# ADE-25_13cm.net
KiCad netlist of a schematic drawn in EAGLE
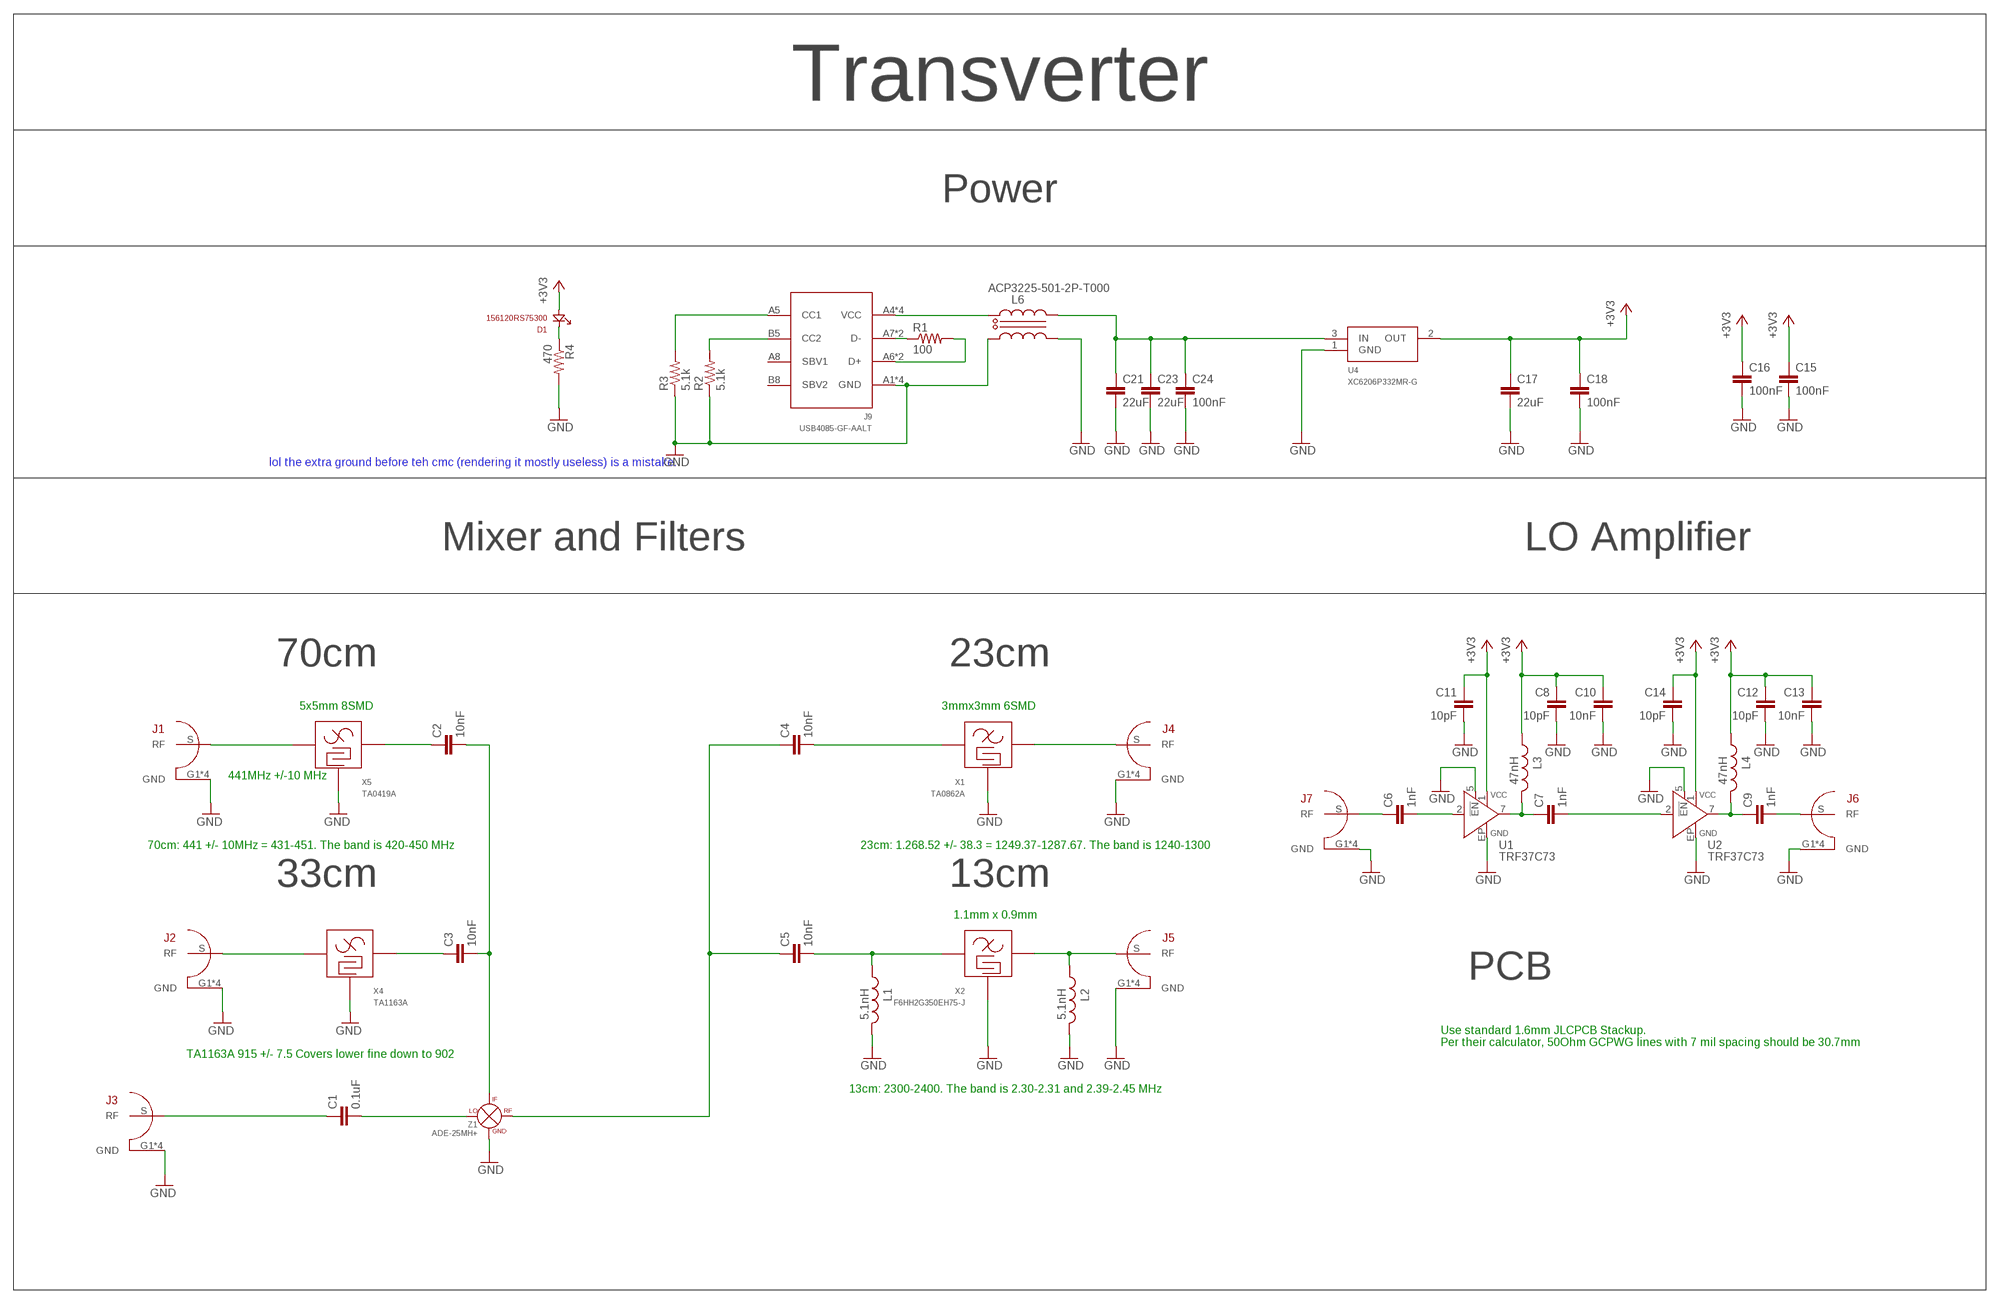
[diagram p0: schematic, sheet 1]

(export (version "E")
  (design (tool "Eeschema 10.0.6"))
  (components
    (comp (ref "C1")
      (value "0.1uF")
      (footprint "eagle-import:0603")
      (libsource (lib "eagle-import") (part "0603_CAPACITOR"))
    )
    (comp (ref "C2")
      (value "10nF")
      (footprint "eagle-import:0603")
      (libsource (lib "eagle-import") (part "0603_CAPACITOR"))
    )
    (comp (ref "C3")
      (value "10nF")
      (footprint "eagle-import:0603")
      (libsource (lib "eagle-import") (part "0603_CAPACITOR"))
    )
    (comp (ref "C4")
      (value "10nF")
      (footprint "eagle-import:0603")
      (libsource (lib "eagle-import") (part "0603_CAPACITOR"))
    )
    (comp (ref "C5")
      (value "10nF")
      (footprint "eagle-import:0603")
      (libsource (lib "eagle-import") (part "0603_CAPACITOR"))
    )
    (comp (ref "C6")
      (value "1nF")
      (footprint "eagle-import:0603")
      (libsource (lib "eagle-import") (part "0603_CAPACITOR"))
    )
    (comp (ref "C7")
      (value "1nF")
      (footprint "eagle-import:0603")
      (libsource (lib "eagle-import") (part "0603_CAPACITOR"))
    )
    (comp (ref "C8")
      (value "10pF")
      (footprint "eagle-import:0402_INDUCTOR")
      (libsource (lib "eagle-import") (part "0402_CAPACITOR"))
    )
    (comp (ref "C9")
      (value "1nF")
      (footprint "eagle-import:0603")
      (libsource (lib "eagle-import") (part "0603_CAPACITOR"))
    )
    (comp (ref "C10")
      (value "10nF")
      (footprint "eagle-import:0402_INDUCTOR")
      (libsource (lib "eagle-import") (part "0402_CAPACITOR"))
    )
    (comp (ref "C11")
      (value "10pF")
      (footprint "eagle-import:0402_INDUCTOR")
      (libsource (lib "eagle-import") (part "0402_CAPACITOR"))
    )
    (comp (ref "C12")
      (value "10pF")
      (footprint "eagle-import:0402_INDUCTOR")
      (libsource (lib "eagle-import") (part "0402_CAPACITOR"))
    )
    (comp (ref "C13")
      (value "10nF")
      (footprint "eagle-import:0402_INDUCTOR")
      (libsource (lib "eagle-import") (part "0402_CAPACITOR"))
    )
    (comp (ref "C14")
      (value "10pF")
      (footprint "eagle-import:0402_INDUCTOR")
      (libsource (lib "eagle-import") (part "0402_CAPACITOR"))
    )
    (comp (ref "C15")
      (value "100nF")
      (footprint "eagle-import:0603")
      (libsource (lib "eagle-import") (part "0603_CAPACITOR"))
    )
    (comp (ref "C16")
      (value "100nF")
      (footprint "eagle-import:0603")
      (libsource (lib "eagle-import") (part "0603_CAPACITOR"))
    )
    (comp (ref "C17")
      (value "22uF")
      (footprint "eagle-import:C1206")
      (libsource (lib "eagle-import") (part "C-EUC1206"))
    )
    (comp (ref "C18")
      (value "100nF")
      (footprint "eagle-import:0603")
      (libsource (lib "eagle-import") (part "0603_CAPACITOR"))
    )
    (comp (ref "C21")
      (value "22uF")
      (footprint "eagle-import:C1206")
      (libsource (lib "eagle-import") (part "C-EUC1206"))
    )
    (comp (ref "C23")
      (value "22uF")
      (footprint "eagle-import:C1206")
      (libsource (lib "eagle-import") (part "C-EUC1206"))
    )
    (comp (ref "C24")
      (value "100nF")
      (footprint "eagle-import:0603")
      (libsource (lib "eagle-import") (part "0603_CAPACITOR"))
    )
    (comp (ref "D1")
      (value "156120RS75300")
      (footprint "eagle-import:1206_REV")
      (fields (field (name "PARTNO") "732-5031-1-ND"))
      (libsource (lib "eagle-import") (part "156120RS75300"))
    )
    (comp (ref "J1")
      (value "0733910070")
      (footprint "eagle-import:CONREVSMA008-G")
      (fields (field (name "PARTNO") "WM5544-ND"))
      (libsource (lib "eagle-import") (part "0733910070"))
    )
    (comp (ref "J2")
      (value "0733910070")
      (footprint "eagle-import:CONREVSMA008-G")
      (fields (field (name "PARTNO") "WM5544-ND"))
      (libsource (lib "eagle-import") (part "0733910070"))
    )
    (comp (ref "J3")
      (value "0733910070")
      (footprint "eagle-import:CONREVSMA008-G")
      (fields (field (name "PARTNO") "WM5544-ND"))
      (libsource (lib "eagle-import") (part "0733910070"))
    )
    (comp (ref "J4")
      (value "0733910070")
      (footprint "eagle-import:CONREVSMA008-G")
      (fields (field (name "PARTNO") "WM5544-ND"))
      (libsource (lib "eagle-import") (part "0733910070"))
    )
    (comp (ref "J5")
      (value "0733910070")
      (footprint "eagle-import:CONREVSMA008-G")
      (fields (field (name "PARTNO") "WM5544-ND"))
      (libsource (lib "eagle-import") (part "0733910070"))
    )
    (comp (ref "J6")
      (value "0733910070")
      (footprint "eagle-import:CONREVSMA008-G")
      (fields (field (name "PARTNO") "WM5544-ND"))
      (libsource (lib "eagle-import") (part "0733910070"))
    )
    (comp (ref "J7")
      (value "0733910070")
      (footprint "eagle-import:CONREVSMA008-G")
      (fields (field (name "PARTNO") "WM5544-ND"))
      (libsource (lib "eagle-import") (part "0733910070"))
    )
    (comp (ref "J9")
      (value "USB4085-GF-AALT")
      (footprint "eagle-import:USBC2")
      (libsource (lib "eagle-import") (part "USB4085-GF-AALT"))
    )
    (comp (ref "L1")
      (value "5.1nH")
      (footprint "eagle-import:0402_INDUCTOR")
      (libsource (lib "eagle-import") (part "0402_INDUCTOR"))
    )
    (comp (ref "L2")
      (value "5.1nH")
      (footprint "eagle-import:0402_INDUCTOR")
      (libsource (lib "eagle-import") (part "0402_INDUCTOR"))
    )
    (comp (ref "L3")
      (value "47nH")
      (footprint "eagle-import:0402_INDUCTOR")
      (libsource (lib "eagle-import") (part "0402_INDUCTOR"))
    )
    (comp (ref "L4")
      (value "47nH")
      (footprint "eagle-import:0402_INDUCTOR")
      (libsource (lib "eagle-import") (part "0402_INDUCTOR"))
    )
    (comp (ref "L6")
      (value "ACP3225-501-2P-T000")
      (footprint "eagle-import:3225")
      (fields (field (name "PARTNO") "445-172408-1-ND"))
      (libsource (lib "eagle-import") (part "ACP3225-501-2P-T000"))
    )
    (comp (ref "R1")
      (value "100")
      (footprint "eagle-import:0603")
      (libsource (lib "eagle-import") (part "0603_RESISTOR"))
    )
    (comp (ref "R2")
      (value "5.1k")
      (footprint "eagle-import:0603")
      (libsource (lib "eagle-import") (part "0603_RESISTOR"))
    )
    (comp (ref "R3")
      (value "5.1k")
      (footprint "eagle-import:0603")
      (libsource (lib "eagle-import") (part "0603_RESISTOR"))
    )
    (comp (ref "R4")
      (value "470")
      (footprint "eagle-import:0603")
      (libsource (lib "eagle-import") (part "0603_RESISTOR"))
    )
    (comp (ref "U1")
      (value "TRF37C73")
      (footprint "eagle-import:8WSON2X2")
      (libsource (lib "eagle-import") (part "TRF37C73"))
    )
    (comp (ref "U2")
      (value "TRF37C73")
      (footprint "eagle-import:8WSON2X2")
      (libsource (lib "eagle-import") (part "TRF37C73"))
    )
    (comp (ref "U4")
      (value "XC6206P332MR-G")
      (footprint "eagle-import:SOT23-3_CENTERED")
      (libsource (lib "eagle-import") (part "XC6206P332MR-G"))
    )
    (comp (ref "X1")
      (value "TA0862A")
      (footprint "eagle-import:TA0862A")
      (fields (field (name "PARTNO") "4606-TA0862ACT-ND"))
      (libsource (lib "eagle-import") (part "TA0862A"))
    )
    (comp (ref "X2")
      (value "F6HH2G350EH75-J")
      (footprint "eagle-import:EH75")
      (fields (field (name "PARTNO") "587-F6HH2G350EH75-JCT-ND"))
      (libsource (lib "eagle-import") (part "F6HH2G350EH75-J"))
    )
    (comp (ref "X4")
      (value "TA1163A")
      (footprint "eagle-import:TA0862A")
      (fields (field (name "PARTNO") "4606-TA0862ACT-ND"))
      (libsource (lib "eagle-import") (part "TA0862A"))
    )
    (comp (ref "X5")
      (value "TA0419A")
      (footprint "eagle-import:TAO419")
      (fields (field (name "PARTNO") "4606-TA0419ACT-ND"))
      (libsource (lib "eagle-import") (part "TA0419A"))
    )
    (comp (ref "Z1")
      (value "ADE-25MH+")
      (footprint "eagle-import:CD")
      (fields (field (name "PARTNO") "3157-ADE-25MH+CT-ND"))
      (libsource (lib "eagle-import") (part "ADE-25MH+"))
    )
  )
  (nets
    (net (code "1") (name "+3V3") (class "Default")
      (node (ref "C10") (pin "P$1") (pinfunction "1_P$1") (pintype "passive"))
      (node (ref "C11") (pin "P$1") (pinfunction "1_P$1") (pintype "passive"))
      (node (ref "C12") (pin "P$1") (pinfunction "1_P$1") (pintype "passive"))
      (node (ref "C13") (pin "P$1") (pinfunction "1_P$1") (pintype "passive"))
      (node (ref "C14") (pin "P$1") (pinfunction "1_P$1") (pintype "passive"))
      (node (ref "C15") (pin "1") (pinfunction "1_1") (pintype "passive"))
      (node (ref "C16") (pin "1") (pinfunction "1_1") (pintype "passive"))
      (node (ref "C17") (pin "1") (pinfunction "1_1") (pintype "passive"))
      (node (ref "C18") (pin "1") (pinfunction "1_1") (pintype "passive"))
      (node (ref "C8") (pin "P$1") (pinfunction "1_P$1") (pintype "passive"))
      (node (ref "D1") (pin "A") (pinfunction "A_A") (pintype "bidirectional"))
      (node (ref "L3") (pin "P$1") (pinfunction "P$1_P$1") (pintype "bidirectional"))
      (node (ref "L4") (pin "P$1") (pinfunction "P$1_P$1") (pintype "bidirectional"))
      (node (ref "U1") (pin "1") (pinfunction "+VS_1") (pintype "input"))
      (node (ref "U2") (pin "1") (pinfunction "+VS_1") (pintype "input"))
      (node (ref "U4") (pin "2") (pinfunction "OUT_2") (pintype "bidirectional"))
    )
    (net (code "2") (name "GND") (class "Default")
      (node (ref "C10") (pin "P$2") (pinfunction "2_P$2") (pintype "passive"))
      (node (ref "C11") (pin "P$2") (pinfunction "2_P$2") (pintype "passive"))
      (node (ref "C12") (pin "P$2") (pinfunction "2_P$2") (pintype "passive"))
      (node (ref "C13") (pin "P$2") (pinfunction "2_P$2") (pintype "passive"))
      (node (ref "C14") (pin "P$2") (pinfunction "2_P$2") (pintype "passive"))
      (node (ref "C15") (pin "2") (pinfunction "2_2") (pintype "passive"))
      (node (ref "C16") (pin "2") (pinfunction "2_2") (pintype "passive"))
      (node (ref "C17") (pin "2") (pinfunction "2_2") (pintype "passive"))
      (node (ref "C18") (pin "2") (pinfunction "2_2") (pintype "passive"))
      (node (ref "C21") (pin "2") (pinfunction "2_2") (pintype "passive"))
      (node (ref "C23") (pin "2") (pinfunction "2_2") (pintype "passive"))
      (node (ref "C24") (pin "2") (pinfunction "2_2") (pintype "passive"))
      (node (ref "C8") (pin "P$2") (pinfunction "2_P$2") (pintype "passive"))
      (node (ref "J1") (pin "G1") (pinfunction "GND_G1") (pintype "bidirectional"))
      (node (ref "J1") (pin "G2") (pinfunction "GND_G2") (pintype "bidirectional"))
      (node (ref "J1") (pin "G3") (pinfunction "GND_G3") (pintype "bidirectional"))
      (node (ref "J1") (pin "G4") (pinfunction "GND_G4") (pintype "bidirectional"))
      (node (ref "J2") (pin "G1") (pinfunction "GND_G1") (pintype "bidirectional"))
      (node (ref "J2") (pin "G2") (pinfunction "GND_G2") (pintype "bidirectional"))
      (node (ref "J2") (pin "G3") (pinfunction "GND_G3") (pintype "bidirectional"))
      (node (ref "J2") (pin "G4") (pinfunction "GND_G4") (pintype "bidirectional"))
      (node (ref "J3") (pin "G1") (pinfunction "GND_G1") (pintype "bidirectional"))
      (node (ref "J3") (pin "G2") (pinfunction "GND_G2") (pintype "bidirectional"))
      (node (ref "J3") (pin "G3") (pinfunction "GND_G3") (pintype "bidirectional"))
      (node (ref "J3") (pin "G4") (pinfunction "GND_G4") (pintype "bidirectional"))
      (node (ref "J4") (pin "G1") (pinfunction "GND_G1") (pintype "bidirectional"))
      (node (ref "J4") (pin "G2") (pinfunction "GND_G2") (pintype "bidirectional"))
      (node (ref "J4") (pin "G3") (pinfunction "GND_G3") (pintype "bidirectional"))
      (node (ref "J4") (pin "G4") (pinfunction "GND_G4") (pintype "bidirectional"))
      (node (ref "J5") (pin "G1") (pinfunction "GND_G1") (pintype "bidirectional"))
      (node (ref "J5") (pin "G2") (pinfunction "GND_G2") (pintype "bidirectional"))
      (node (ref "J5") (pin "G3") (pinfunction "GND_G3") (pintype "bidirectional"))
      (node (ref "J5") (pin "G4") (pinfunction "GND_G4") (pintype "bidirectional"))
      (node (ref "J6") (pin "G1") (pinfunction "GND_G1") (pintype "bidirectional"))
      (node (ref "J6") (pin "G2") (pinfunction "GND_G2") (pintype "bidirectional"))
      (node (ref "J6") (pin "G3") (pinfunction "GND_G3") (pintype "bidirectional"))
      (node (ref "J6") (pin "G4") (pinfunction "GND_G4") (pintype "bidirectional"))
      (node (ref "J7") (pin "G1") (pinfunction "GND_G1") (pintype "bidirectional"))
      (node (ref "J7") (pin "G2") (pinfunction "GND_G2") (pintype "bidirectional"))
      (node (ref "J7") (pin "G3") (pinfunction "GND_G3") (pintype "bidirectional"))
      (node (ref "J7") (pin "G4") (pinfunction "GND_G4") (pintype "bidirectional"))
      (node (ref "J9") (pin "A1") (pinfunction "GND_A1") (pintype "bidirectional"))
      (node (ref "J9") (pin "A12") (pinfunction "GND_A12") (pintype "bidirectional"))
      (node (ref "J9") (pin "B1") (pinfunction "GND_B1") (pintype "bidirectional"))
      (node (ref "J9") (pin "B12") (pinfunction "GND_B12") (pintype "bidirectional"))
      (node (ref "L1") (pin "P$2") (pinfunction "P$2_P$2") (pintype "bidirectional"))
      (node (ref "L2") (pin "P$2") (pinfunction "P$2_P$2") (pintype "bidirectional"))
      (node (ref "L6") (pin "2") (pinfunction "2IN_2") (pintype "bidirectional"))
      (node (ref "L6") (pin "3") (pinfunction "2OUT_3") (pintype "bidirectional"))
      (node (ref "R2") (pin "1") (pinfunction "1_1") (pintype "passive"))
      (node (ref "R3") (pin "1") (pinfunction "1_1") (pintype "passive"))
      (node (ref "R4") (pin "2") (pinfunction "2_2") (pintype "passive"))
      (node (ref "U1") (pin "5") (pinfunction "~{EN}_5") (pintype "bidirectional"))
      (node (ref "U1") (pin "EP") (pinfunction "-VS_EP") (pintype "input"))
      (node (ref "U2") (pin "5") (pinfunction "~{EN}_5") (pintype "bidirectional"))
      (node (ref "U2") (pin "EP") (pinfunction "-VS_EP") (pintype "input"))
      (node (ref "U4") (pin "1") (pinfunction "GND_1") (pintype "bidirectional"))
      (node (ref "X1") (pin "A") (pinfunction "GND_A") (pintype "bidirectional"))
      (node (ref "X1") (pin "C") (pinfunction "GND_C") (pintype "bidirectional"))
      (node (ref "X1") (pin "D") (pinfunction "GND_D") (pintype "bidirectional"))
      (node (ref "X1") (pin "F") (pinfunction "GND_F") (pintype "bidirectional"))
      (node (ref "X2") (pin "2") (pinfunction "GND_2") (pintype "bidirectional"))
      (node (ref "X2") (pin "3") (pinfunction "GND_3") (pintype "bidirectional"))
      (node (ref "X2") (pin "5") (pinfunction "GND_5") (pintype "bidirectional"))
      (node (ref "X4") (pin "A") (pinfunction "GND_A") (pintype "bidirectional"))
      (node (ref "X4") (pin "C") (pinfunction "GND_C") (pintype "bidirectional"))
      (node (ref "X4") (pin "D") (pinfunction "GND_D") (pintype "bidirectional"))
      (node (ref "X4") (pin "F") (pinfunction "GND_F") (pintype "bidirectional"))
      (node (ref "X5") (pin "1") (pinfunction "GND_1") (pintype "bidirectional"))
      (node (ref "X5") (pin "3") (pinfunction "GND_3") (pintype "bidirectional"))
      (node (ref "X5") (pin "4") (pinfunction "GND_4") (pintype "bidirectional"))
      (node (ref "X5") (pin "5") (pinfunction "GND_5") (pintype "bidirectional"))
      (node (ref "X5") (pin "7") (pinfunction "GND_7") (pintype "bidirectional"))
      (node (ref "X5") (pin "8") (pinfunction "GND_8") (pintype "bidirectional"))
      (node (ref "Z1") (pin "1") (pinfunction "GND_1") (pintype "bidirectional"))
      (node (ref "Z1") (pin "4") (pinfunction "GND_4") (pintype "bidirectional"))
      (node (ref "Z1") (pin "5") (pinfunction "GND_5") (pintype "bidirectional"))
    )
    (net (code "3") (name "Net-(D1-PadK)") (class "Default")
      (node (ref "D1") (pin "K") (pinfunction "K_K") (pintype "bidirectional"))
      (node (ref "R4") (pin "1") (pinfunction "1_1") (pintype "passive"))
    )
    (net (code "4") (name "Net-(J1-RF)") (class "Default")
      (node (ref "J1") (pin "S") (pinfunction "RF_S") (pintype "bidirectional"))
      (node (ref "X5") (pin "6") (pinfunction "P$2_6") (pintype "bidirectional"))
    )
    (net (code "5") (name "Net-(J2-RF)") (class "Default")
      (node (ref "J2") (pin "S") (pinfunction "RF_S") (pintype "bidirectional"))
      (node (ref "X4") (pin "E") (pinfunction "P$2_E") (pintype "bidirectional"))
    )
    (net (code "6") (name "Net-(J3-RF)") (class "Default")
      (node (ref "C1") (pin "1") (pinfunction "1_1") (pintype "passive"))
      (node (ref "J3") (pin "S") (pinfunction "RF_S") (pintype "bidirectional"))
    )
    (net (code "7") (name "Net-(J4-RF)") (class "Default")
      (node (ref "J4") (pin "S") (pinfunction "RF_S") (pintype "bidirectional"))
      (node (ref "X1") (pin "E") (pinfunction "P$2_E") (pintype "bidirectional"))
    )
    (net (code "8") (name "Net-(J5-RF)") (class "Default")
      (node (ref "J5") (pin "S") (pinfunction "RF_S") (pintype "bidirectional"))
      (node (ref "L2") (pin "P$1") (pinfunction "P$1_P$1") (pintype "bidirectional"))
      (node (ref "X2") (pin "4") (pinfunction "P$2_4") (pintype "bidirectional"))
    )
    (net (code "9") (name "Net-(J6-RF)") (class "Default")
      (node (ref "C9") (pin "2") (pinfunction "2_2") (pintype "passive"))
      (node (ref "J6") (pin "S") (pinfunction "RF_S") (pintype "bidirectional"))
    )
    (net (code "10") (name "Net-(J7-RF)") (class "Default")
      (node (ref "C6") (pin "1") (pinfunction "1_1") (pintype "passive"))
      (node (ref "J7") (pin "S") (pinfunction "RF_S") (pintype "bidirectional"))
    )
    (net (code "11") (name "Net-(J9-CC1)") (class "Default")
      (node (ref "J9") (pin "A5") (pinfunction "CC1_A5") (pintype "bidirectional"))
      (node (ref "R3") (pin "2") (pinfunction "2_2") (pintype "passive"))
    )
    (net (code "12") (name "Net-(J9-CC2)") (class "Default")
      (node (ref "J9") (pin "B5") (pinfunction "CC2_B5") (pintype "bidirectional"))
      (node (ref "R2") (pin "2") (pinfunction "2_2") (pintype "passive"))
    )
    (net (code "13") (name "Net-(J9-D+-PadA6)") (class "Default")
      (node (ref "J9") (pin "A6") (pinfunction "D+_A6") (pintype "bidirectional"))
      (node (ref "J9") (pin "B6") (pinfunction "D+_B6") (pintype "bidirectional"))
      (node (ref "R1") (pin "2") (pinfunction "2_2") (pintype "passive"))
    )
    (net (code "14") (name "Net-(J9-D--PadA7)") (class "Default")
      (node (ref "J9") (pin "A7") (pinfunction "D-_A7") (pintype "bidirectional"))
      (node (ref "J9") (pin "B7") (pinfunction "D-_B7") (pintype "bidirectional"))
      (node (ref "R1") (pin "1") (pinfunction "1_1") (pintype "passive"))
    )
    (net (code "15") (name "Net-(L6-1IN)") (class "Default")
      (node (ref "J9") (pin "A4") (pinfunction "VCC_A4") (pintype "bidirectional"))
      (node (ref "J9") (pin "A9") (pinfunction "VCC_A9") (pintype "bidirectional"))
      (node (ref "J9") (pin "B4") (pinfunction "VCC_B4") (pintype "bidirectional"))
      (node (ref "J9") (pin "B9") (pinfunction "VCC_B9") (pintype "bidirectional"))
      (node (ref "L6") (pin "1") (pinfunction "1IN_1") (pintype "bidirectional"))
    )
    (net (code "16") (name "Net-(L6-1OUT)") (class "Default")
      (node (ref "C21") (pin "1") (pinfunction "1_1") (pintype "passive"))
      (node (ref "C23") (pin "1") (pinfunction "1_1") (pintype "passive"))
      (node (ref "C24") (pin "1") (pinfunction "1_1") (pintype "passive"))
      (node (ref "L6") (pin "4") (pinfunction "1OUT_4") (pintype "bidirectional"))
      (node (ref "U4") (pin "3") (pinfunction "IN_3") (pintype "bidirectional"))
    )
    (net (code "17") (name "Net-(U1-IN)") (class "Default")
      (node (ref "C6") (pin "2") (pinfunction "2_2") (pintype "passive"))
      (node (ref "U1") (pin "2") (pinfunction "IN_2") (pintype "input"))
    )
    (net (code "18") (name "Net-(U1-OUT)") (class "Default")
      (node (ref "C7") (pin "1") (pinfunction "1_1") (pintype "passive"))
      (node (ref "L3") (pin "P$2") (pinfunction "P$2_P$2") (pintype "bidirectional"))
      (node (ref "U1") (pin "7") (pinfunction "OUT_7") (pintype "output"))
    )
    (net (code "19") (name "Net-(U2-IN)") (class "Default")
      (node (ref "C7") (pin "2") (pinfunction "2_2") (pintype "passive"))
      (node (ref "U2") (pin "2") (pinfunction "IN_2") (pintype "input"))
    )
    (net (code "20") (name "Net-(U2-OUT)") (class "Default")
      (node (ref "C9") (pin "1") (pinfunction "1_1") (pintype "passive"))
      (node (ref "L4") (pin "P$2") (pinfunction "P$2_P$2") (pintype "bidirectional"))
      (node (ref "U2") (pin "7") (pinfunction "OUT_7") (pintype "output"))
    )
    (net (code "21") (name "Net-(X1-P$1)") (class "Default")
      (node (ref "C4") (pin "2") (pinfunction "2_2") (pintype "passive"))
      (node (ref "X1") (pin "B") (pinfunction "P$1_B") (pintype "bidirectional"))
    )
    (net (code "22") (name "Net-(X2-P$1)") (class "Default")
      (node (ref "C5") (pin "2") (pinfunction "2_2") (pintype "passive"))
      (node (ref "L1") (pin "P$1") (pinfunction "P$1_P$1") (pintype "bidirectional"))
      (node (ref "X2") (pin "1") (pinfunction "P$1_1") (pintype "bidirectional"))
    )
    (net (code "23") (name "Net-(X4-P$1)") (class "Default")
      (node (ref "C3") (pin "1") (pinfunction "1_1") (pintype "passive"))
      (node (ref "X4") (pin "B") (pinfunction "P$1_B") (pintype "bidirectional"))
    )
    (net (code "24") (name "Net-(X5-P$1)") (class "Default")
      (node (ref "C2") (pin "1") (pinfunction "1_1") (pintype "passive"))
      (node (ref "X5") (pin "2") (pinfunction "P$1_2") (pintype "bidirectional"))
    )
    (net (code "25") (name "Net-(Z1-IF)") (class "Default")
      (node (ref "C2") (pin "2") (pinfunction "2_2") (pintype "passive"))
      (node (ref "C3") (pin "2") (pinfunction "2_2") (pintype "passive"))
      (node (ref "Z1") (pin "2") (pinfunction "IF_2") (pintype "bidirectional"))
    )
    (net (code "26") (name "Net-(Z1-LO)") (class "Default")
      (node (ref "C1") (pin "2") (pinfunction "2_2") (pintype "passive"))
      (node (ref "Z1") (pin "6") (pinfunction "LO_6") (pintype "bidirectional"))
    )
    (net (code "27") (name "Net-(Z1-RF)") (class "Default")
      (node (ref "C4") (pin "1") (pinfunction "1_1") (pintype "passive"))
      (node (ref "C5") (pin "1") (pinfunction "1_1") (pintype "passive"))
      (node (ref "Z1") (pin "3") (pinfunction "RF_3") (pintype "bidirectional"))
    )
    (net (code "28") (name "unconnected-(J9-SBV1-PadA8)") (class "Default")
      (node (ref "J9") (pin "A8") (pinfunction "SBV1_A8") (pintype "bidirectional"))
    )
    (net (code "29") (name "unconnected-(J9-SBV2-PadB8)") (class "Default")
      (node (ref "J9") (pin "B8") (pinfunction "SBV2_B8") (pintype "bidirectional"))
    )
  )
)
